# MainBoard.net
KiCad netlist of a schematic drawn in EAGLE
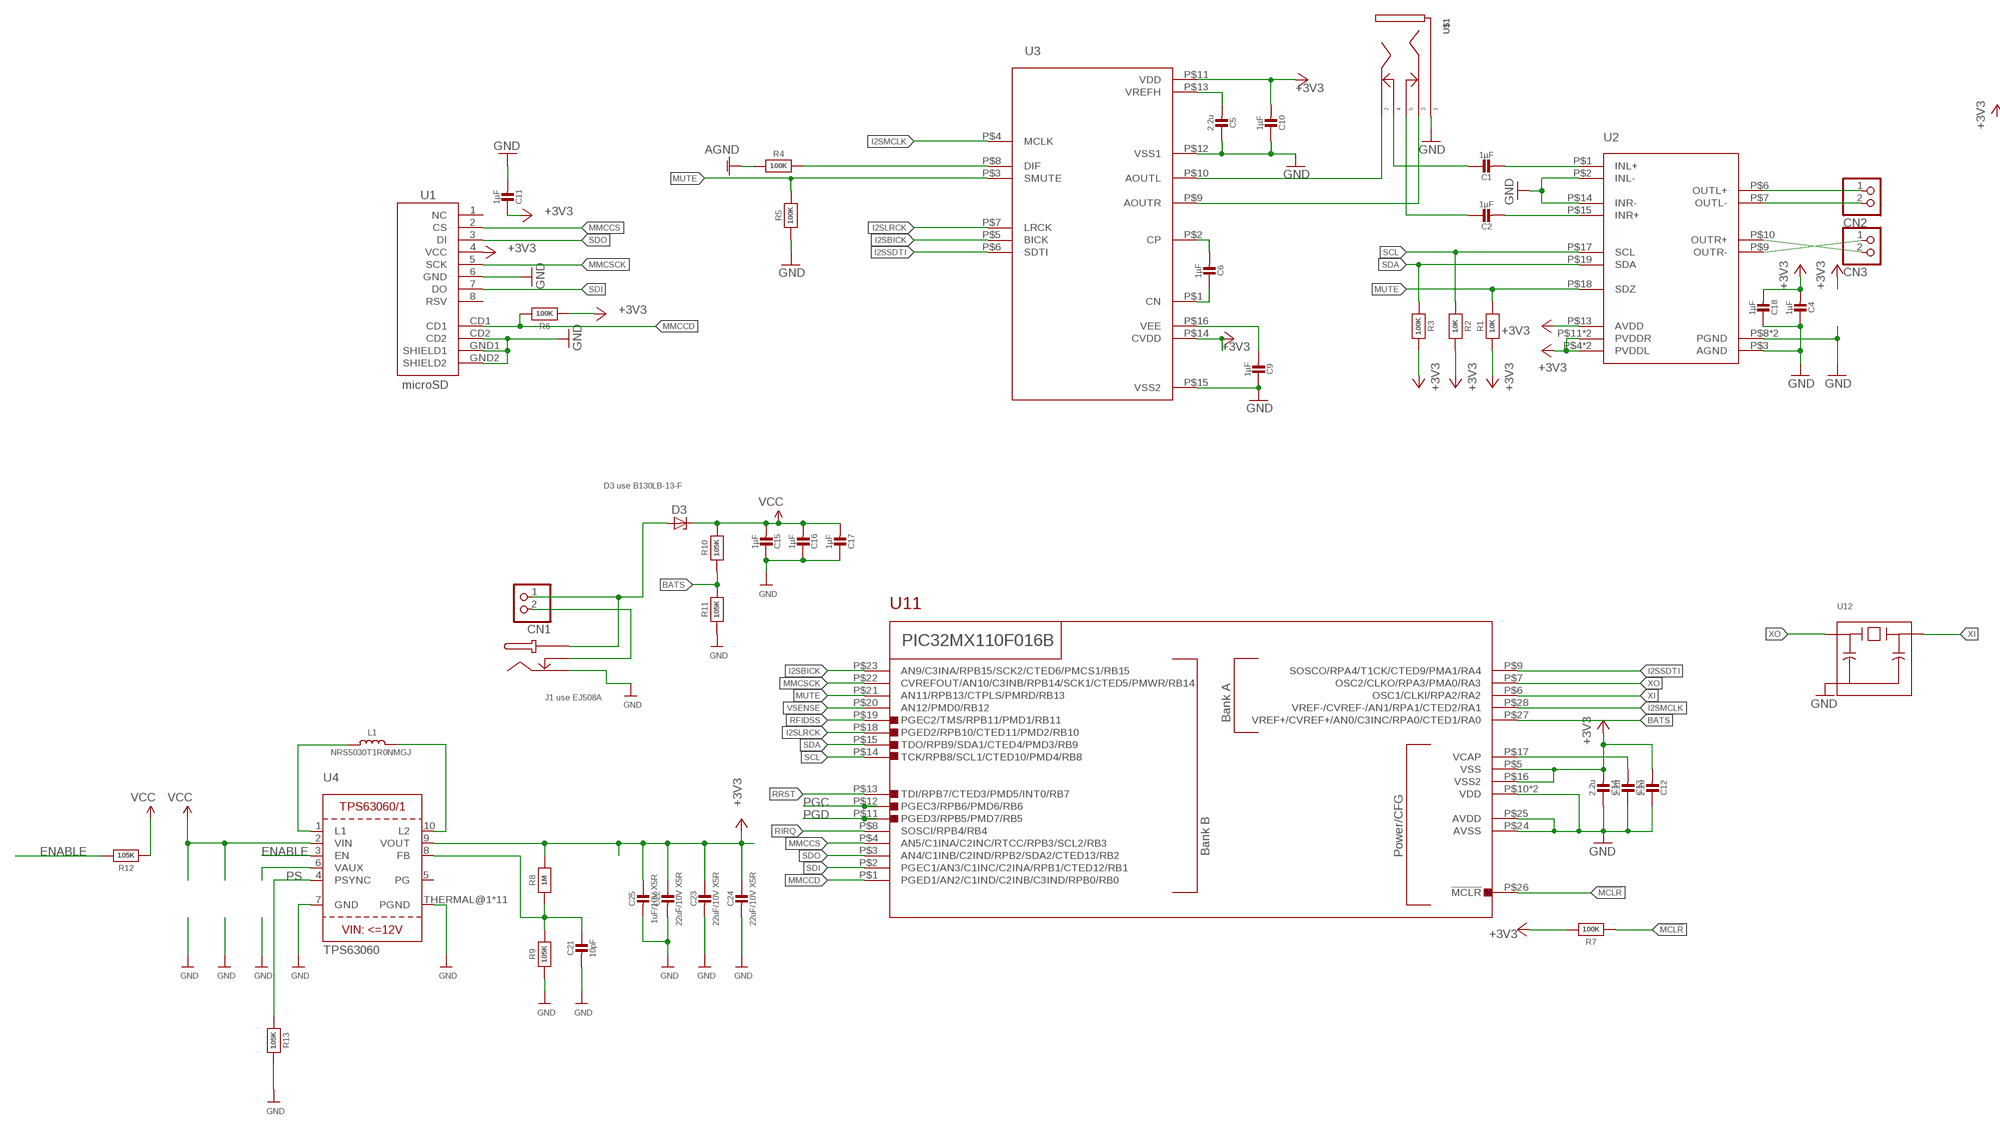
[diagram p0: schematic, sheet 1, part 1 of 2]
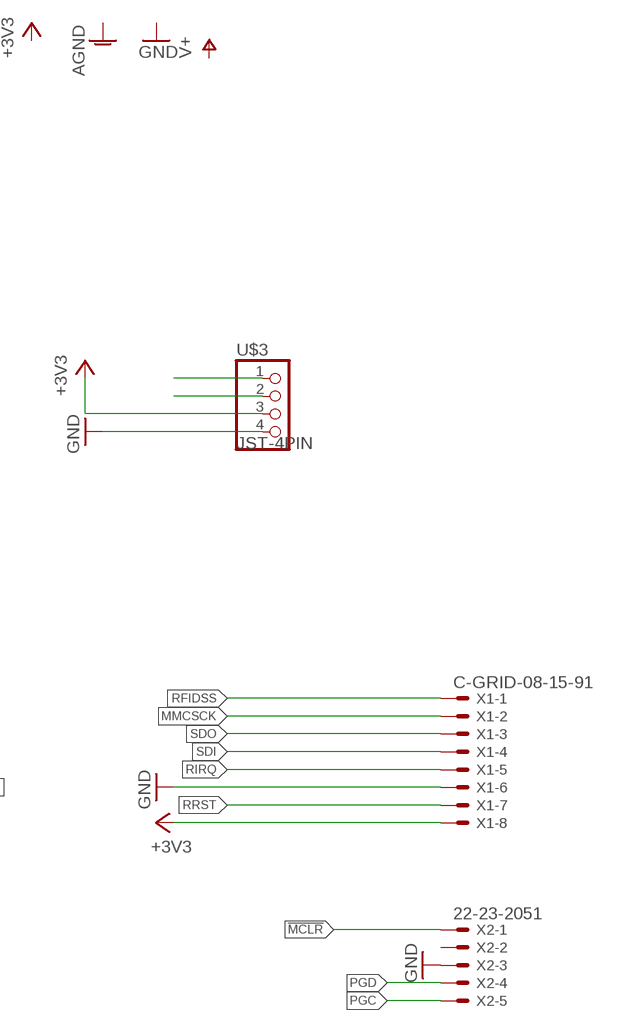
[diagram p1: schematic, sheet 1, part 2 of 2]

(export (version "E")
  (design (tool "Eeschema 10.0.6"))
  (components
    (comp (ref "C1")
      (value "1µF")
      (footprint "eagle-import:0603-NO")
      (libsource (lib "eagle-import") (part "CAP_CERAMIC0603_NO"))
    )
    (comp (ref "C2")
      (value "1µF")
      (footprint "eagle-import:0603-NO")
      (libsource (lib "eagle-import") (part "CAP_CERAMIC0603_NO"))
    )
    (comp (ref "C4")
      (value "1µF")
      (footprint "eagle-import:0805-NO")
      (libsource (lib "eagle-import") (part "CAP_CERAMIC0805-NOOUTLINE"))
    )
    (comp (ref "C5")
      (value "2.2u")
      (footprint "eagle-import:0603-NO")
      (libsource (lib "eagle-import") (part "CAP_CERAMIC0603_NO"))
    )
    (comp (ref "C6")
      (value "1µF")
      (footprint "eagle-import:0603-NO")
      (libsource (lib "eagle-import") (part "CAP_CERAMIC0603_NO"))
    )
    (comp (ref "C9")
      (value "1µF")
      (footprint "eagle-import:0603-NO")
      (libsource (lib "eagle-import") (part "CAP_CERAMIC0603_NO"))
    )
    (comp (ref "C10")
      (value "1µF")
      (footprint "eagle-import:0603-NO")
      (libsource (lib "eagle-import") (part "CAP_CERAMIC0603_NO"))
    )
    (comp (ref "C11")
      (value "1µF")
      (footprint "eagle-import:0603-NO")
      (libsource (lib "eagle-import") (part "CAP_CERAMIC0603_NO"))
    )
    (comp (ref "C12")
      (value "2.2u")
      (footprint "eagle-import:0603-NO")
      (libsource (lib "eagle-import") (part "CAP_CERAMIC0603_NO"))
    )
    (comp (ref "C13")
      (value "2.2u")
      (footprint "eagle-import:0603-NO")
      (libsource (lib "eagle-import") (part "CAP_CERAMIC0603_NO"))
    )
    (comp (ref "C14")
      (value "2.2u")
      (footprint "eagle-import:0603-NO")
      (libsource (lib "eagle-import") (part "CAP_CERAMIC0603_NO"))
    )
    (comp (ref "C15")
      (value "1µF")
      (footprint "eagle-import:0805-NO")
      (libsource (lib "eagle-import") (part "CAP_CERAMIC0805-NOOUTLINE"))
    )
    (comp (ref "C16")
      (value "1µF")
      (footprint "eagle-import:0805-NO")
      (libsource (lib "eagle-import") (part "CAP_CERAMIC0805-NOOUTLINE"))
    )
    (comp (ref "C17")
      (value "1µF")
      (footprint "eagle-import:0805-NO")
      (libsource (lib "eagle-import") (part "CAP_CERAMIC0805-NOOUTLINE"))
    )
    (comp (ref "C18")
      (value "1µF")
      (footprint "eagle-import:0805-NO")
      (libsource (lib "eagle-import") (part "CAP_CERAMIC0805-NOOUTLINE"))
    )
    (comp (ref "C21")
      (value "10pF")
      (footprint "eagle-import:0603-NO")
      (libsource (lib "eagle-import") (part "CAP_CERAMIC0603_NO"))
    )
    (comp (ref "C22")
      (value "22uF/10V X5R")
      (footprint "eagle-import:0805-NO")
      (libsource (lib "eagle-import") (part "CAP_CERAMIC0805-NOOUTLINE"))
    )
    (comp (ref "C23")
      (value "22uF/10V X5R")
      (footprint "eagle-import:0805-NO")
      (libsource (lib "eagle-import") (part "CAP_CERAMIC0805-NOOUTLINE"))
    )
    (comp (ref "C24")
      (value "22uF/10V X5R")
      (footprint "eagle-import:0805-NO")
      (libsource (lib "eagle-import") (part "CAP_CERAMIC0805-NOOUTLINE"))
    )
    (comp (ref "C25")
      (value "1uF/10V X5R")
      (footprint "eagle-import:0805-NO")
      (libsource (lib "eagle-import") (part "CAP_CERAMIC0805-NOOUTLINE"))
    )
    (comp (ref "CN1")
      (value "JST_2PIN-SMT-RA")
      (footprint "eagle-import:JST-PH-2-SMT-RA")
      (libsource (lib "eagle-import") (part "JST_2PIN-SMT-RA"))
    )
    (comp (ref "CN2")
      (value "JST_2PIN-SMT-RA")
      (footprint "eagle-import:JST-PH-2-SMT-RA")
      (libsource (lib "eagle-import") (part "JST_2PIN-SMT-RA"))
    )
    (comp (ref "CN3")
      (value "JST_2PIN-SMT-RA")
      (footprint "eagle-import:JST-PH-2-SMT-RA")
      (libsource (lib "eagle-import") (part "JST_2PIN-SMT-RA"))
    )
    (comp (ref "D3")
      (value "ZENER-DIODESOD80C")
      (footprint "eagle-import:SOD80C")
      (libsource (lib "eagle-import") (part "ZENER-DIODESOD80C"))
    )
    (comp (ref "L1")
      (value "NRS5030T1R0NMGJ")
      (footprint "eagle-import:INDUCTOR_5X5MM_TDK_VLC5045")
      (libsource (lib "eagle-import") (part "INDUCTORTDK_VLC5045"))
    )
    (comp (ref "R1")
      (value "10K")
      (footprint "eagle-import:0603-NO")
      (libsource (lib "eagle-import") (part "RESISTOR_0603_NOOUT"))
    )
    (comp (ref "R2")
      (value "10K")
      (footprint "eagle-import:0603-NO")
      (libsource (lib "eagle-import") (part "RESISTOR_0603_NOOUT"))
    )
    (comp (ref "R3")
      (value "100K")
      (footprint "eagle-import:0603-NO")
      (libsource (lib "eagle-import") (part "RESISTOR_0603_NOOUT"))
    )
    (comp (ref "R4")
      (value "100K")
      (footprint "eagle-import:0603-NO")
      (libsource (lib "eagle-import") (part "RESISTOR_0603_NOOUT"))
    )
    (comp (ref "R5")
      (value "100K")
      (footprint "eagle-import:0603-NO")
      (libsource (lib "eagle-import") (part "RESISTOR_0603_NOOUT"))
    )
    (comp (ref "R6")
      (value "100K")
      (footprint "eagle-import:0603-NO")
      (libsource (lib "eagle-import") (part "RESISTOR_0603_NOOUT"))
    )
    (comp (ref "R7")
      (value "100K")
      (footprint "eagle-import:0603-NO")
      (libsource (lib "eagle-import") (part "RESISTOR_0603_NOOUT"))
    )
    (comp (ref "R8")
      (value "1M")
      (footprint "eagle-import:0603-NO")
      (libsource (lib "eagle-import") (part "RESISTOR_0603_NOOUT"))
    )
    (comp (ref "R9")
      (value "105K")
      (footprint "eagle-import:0603-NO")
      (libsource (lib "eagle-import") (part "RESISTOR_0603_NOOUT"))
    )
    (comp (ref "R10")
      (value "105K")
      (footprint "eagle-import:0603-NO")
      (libsource (lib "eagle-import") (part "RESISTOR_0603_NOOUT"))
    )
    (comp (ref "R11")
      (value "105K")
      (footprint "eagle-import:0603-NO")
      (libsource (lib "eagle-import") (part "RESISTOR_0603_NOOUT"))
    )
    (comp (ref "R12")
      (value "105K")
      (footprint "eagle-import:0603-NO")
      (libsource (lib "eagle-import") (part "RESISTOR_0603_NOOUT"))
    )
    (comp (ref "R13")
      (value "105K")
      (footprint "eagle-import:0603-NO")
      (libsource (lib "eagle-import") (part "RESISTOR_0603_NOOUT"))
    )
    (comp (ref "U$1")
      (value "3,5MMPHONO")
      (footprint "eagle-import:SJ1-351X")
      (libsource (lib "eagle-import") (part "3,5MMPHONO"))
    )
    (comp (ref "U$2")
      (value "PJ-002AH")
      (footprint "eagle-import:PJ-002AH-SMT")
      (libsource (lib "eagle-import") (part "PJ-002AH"))
    )
    (comp (ref "U$3")
      (value "JST-4PIN")
      (footprint "eagle-import:JST-PH-4-SMT-RA")
      (libsource (lib "eagle-import") (part "JST-4PIN"))
    )
    (comp (ref "U1")
      (value "microSD")
      (footprint "eagle-import:MICRO-SD-SOCKET-PP")
      (libsource (lib "eagle-import") (part "USD-SOCKETSMD"))
    )
    (comp (ref "U2")
      (value "TPA2016")
      (footprint "eagle-import:S-PWQFN-N20")
      (libsource (lib "eagle-import") (part "TPA2016"))
    )
    (comp (ref "U3")
      (value "AK4430ET")
      (footprint "eagle-import:16TSSOP")
      (libsource (lib "eagle-import") (part "AK4430ET"))
    )
    (comp (ref "U4")
      (value "TPS63060")
      (footprint "eagle-import:PWSON-N10")
      (libsource (lib "eagle-import") (part "VREG_TPS63060/1"))
    )
    (comp (ref "U11")
      (value "PIC32MX110QFN")
      (footprint "eagle-import:28-QFN")
      (libsource (lib "eagle-import") (part "PIC32MX110QFN"))
    )
    (comp (ref "U12")
      (value "CSTCE")
      (footprint "eagle-import:CSTCE")
      (libsource (lib "eagle-import") (part "CSTCE"))
    )
    (comp (ref "X1")
      (value "C-GRID-08-15-91")
      (footprint "eagle-import:15-91-08")
      (libsource (lib "eagle-import") (part "C-GRID-08-15-91"))
    )
    (comp (ref "X2")
      (value "22-23-2051")
      (footprint "eagle-import:22-23-2051")
      (fields (field (name "MF") "MOLEX"))
      (libsource (lib "eagle-import") (part "22-23-2051"))
    )
  )
  (nets
    (net (code "1") (name "+3V3") (class "Default")
      (node (ref "C10") (pin "2") (pinfunction "2_2") (pintype "passive"))
      (node (ref "C11") (pin "1") (pinfunction "1_1") (pintype "passive"))
      (node (ref "C12") (pin "2") (pinfunction "2_2") (pintype "passive"))
      (node (ref "C14") (pin "2") (pinfunction "2_2") (pintype "passive"))
      (node (ref "C18") (pin "2") (pinfunction "2_2") (pintype "passive"))
      (node (ref "C22") (pin "1") (pinfunction "1_1") (pintype "passive"))
      (node (ref "C23") (pin "1") (pinfunction "1_1") (pintype "passive"))
      (node (ref "C24") (pin "1") (pinfunction "1_1") (pintype "passive"))
      (node (ref "C25") (pin "1") (pinfunction "1_1") (pintype "passive"))
      (node (ref "C4") (pin "2") (pinfunction "2_2") (pintype "passive"))
      (node (ref "R1") (pin "1") (pinfunction "1_1") (pintype "passive"))
      (node (ref "R2") (pin "2") (pinfunction "2_2") (pintype "passive"))
      (node (ref "R3") (pin "2") (pinfunction "2_2") (pintype "passive"))
      (node (ref "R6") (pin "1") (pinfunction "1_1") (pintype "passive"))
      (node (ref "R7") (pin "2") (pinfunction "2_2") (pintype "passive"))
      (node (ref "R8") (pin "2") (pinfunction "2_2") (pintype "passive"))
      (node (ref "U$3") (pin "3") (pinfunction "3_3") (pintype "passive"))
      (node (ref "U1") (pin "4") (pinfunction "VCC_4") (pintype "bidirectional"))
      (node (ref "U11") (pin "P$16") (pinfunction "VSS2_P$16") (pintype "bidirectional"))
      (node (ref "U11") (pin "P$5") (pinfunction "VSS_P$5") (pintype "bidirectional"))
      (node (ref "U2") (pin "P$11") (pinfunction "PVDDR_P$11") (pintype "bidirectional"))
      (node (ref "U2") (pin "P$12") (pinfunction "PVDDR_P$12") (pintype "bidirectional"))
      (node (ref "U2") (pin "P$13") (pinfunction "AVDD_P$13") (pintype "bidirectional"))
      (node (ref "U2") (pin "P$4") (pinfunction "PVDDL_P$4") (pintype "bidirectional"))
      (node (ref "U2") (pin "P$5") (pinfunction "PVDDL_P$5") (pintype "bidirectional"))
      (node (ref "U3") (pin "P$11") (pinfunction "VDD_P$11") (pintype "bidirectional"))
      (node (ref "U3") (pin "P$14") (pinfunction "CVDD_P$14") (pintype "bidirectional"))
      (node (ref "U4") (pin "9") (pinfunction "VOUT_9") (pintype "power_in"))
      (node (ref "X1") (pin "8") (pinfunction "S_8") (pintype "passive"))
    )
    (net (code "2") (name "/ENABLE") (class "Default")
      (node (ref "R12") (pin "2") (pinfunction "2_2") (pintype "passive"))
      (node (ref "U4") (pin "3") (pinfunction "EN_3") (pintype "input"))
    )
    (net (code "3") (name "/PS") (class "Default")
      (node (ref "R13") (pin "1") (pinfunction "1_1") (pintype "passive"))
      (node (ref "U4") (pin "4") (pinfunction "PSYNC_4") (pintype "input"))
    )
    (net (code "4") (name "/~{MCLR}") (class "Default")
      (node (ref "R7") (pin "1") (pinfunction "1_1") (pintype "passive"))
      (node (ref "U11") (pin "P$26") (pinfunction "~{MCLR}_P$26") (pintype "bidirectional"))
      (node (ref "X2") (pin "1") (pinfunction "S_1") (pintype "passive"))
    )
    (net (code "5") (name "AGND") (class "Default")
      (node (ref "R4") (pin "1") (pinfunction "1_1") (pintype "passive"))
    )
    (net (code "6") (name "BATS") (class "Default")
      (node (ref "R10") (pin "1") (pinfunction "1_1") (pintype "passive"))
      (node (ref "R11") (pin "2") (pinfunction "2_2") (pintype "passive"))
      (node (ref "U11") (pin "P$27") (pinfunction "VREF+/CVREF+/AN0/C3INC/RPA0/CTED1/RA0_P$27") (pintype "bidirectional"))
    )
    (net (code "7") (name "GND") (class "Default")
      (node (ref "C10") (pin "1") (pinfunction "1_1") (pintype "passive"))
      (node (ref "C11") (pin "2") (pinfunction "2_2") (pintype "passive"))
      (node (ref "C12") (pin "1") (pinfunction "1_1") (pintype "passive"))
      (node (ref "C13") (pin "1") (pinfunction "1_1") (pintype "passive"))
      (node (ref "C14") (pin "1") (pinfunction "1_1") (pintype "passive"))
      (node (ref "C15") (pin "1") (pinfunction "1_1") (pintype "passive"))
      (node (ref "C16") (pin "1") (pinfunction "1_1") (pintype "passive"))
      (node (ref "C17") (pin "1") (pinfunction "1_1") (pintype "passive"))
      (node (ref "C18") (pin "1") (pinfunction "1_1") (pintype "passive"))
      (node (ref "C21") (pin "2") (pinfunction "2_2") (pintype "passive"))
      (node (ref "C22") (pin "2") (pinfunction "2_2") (pintype "passive"))
      (node (ref "C23") (pin "2") (pinfunction "2_2") (pintype "passive"))
      (node (ref "C24") (pin "2") (pinfunction "2_2") (pintype "passive"))
      (node (ref "C25") (pin "2") (pinfunction "2_2") (pintype "passive"))
      (node (ref "C4") (pin "1") (pinfunction "1_1") (pintype "passive"))
      (node (ref "C5") (pin "1") (pinfunction "1_1") (pintype "passive"))
      (node (ref "C9") (pin "1") (pinfunction "1_1") (pintype "passive"))
      (node (ref "R11") (pin "1") (pinfunction "1_1") (pintype "passive"))
      (node (ref "R13") (pin "2") (pinfunction "2_2") (pintype "passive"))
      (node (ref "R5") (pin "1") (pinfunction "1_1") (pintype "passive"))
      (node (ref "R9") (pin "1") (pinfunction "1_1") (pintype "passive"))
      (node (ref "U$1") (pin "1") (pinfunction "1_1") (pintype "bidirectional"))
      (node (ref "U$2") (pin "2") (pinfunction "2_2") (pintype "bidirectional"))
      (node (ref "U$3") (pin "4") (pinfunction "4_4") (pintype "passive"))
      (node (ref "U1") (pin "6") (pinfunction "GND_6") (pintype "bidirectional"))
      (node (ref "U1") (pin "CD2") (pinfunction "CD2_CD2") (pintype "bidirectional"))
      (node (ref "U1") (pin "GND1") (pinfunction "SHIELD1_GND1") (pintype "bidirectional"))
      (node (ref "U1") (pin "GND2") (pinfunction "SHIELD2_GND2") (pintype "bidirectional"))
      (node (ref "U11") (pin "P$10") (pinfunction "VDD_P$10") (pintype "bidirectional"))
      (node (ref "U11") (pin "P$24") (pinfunction "AVSS_P$24") (pintype "bidirectional"))
      (node (ref "U11") (pin "P$25") (pinfunction "AVDD_P$25") (pintype "bidirectional"))
      (node (ref "U11") (pin "P$29") (pinfunction "VDD_P$29") (pintype "bidirectional"))
      (node (ref "U12") (pin "2") (pinfunction "2_2") (pintype "bidirectional"))
      (node (ref "U2") (pin "P$14") (pinfunction "INR-_P$14") (pintype "bidirectional"))
      (node (ref "U2") (pin "P$2") (pinfunction "INL-_P$2") (pintype "bidirectional"))
      (node (ref "U2") (pin "P$21") (pinfunction "PGND_P$21") (pintype "bidirectional"))
      (node (ref "U2") (pin "P$3") (pinfunction "AGND_P$3") (pintype "bidirectional"))
      (node (ref "U2") (pin "P$8") (pinfunction "PGND_P$8") (pintype "bidirectional"))
      (node (ref "U3") (pin "P$12") (pinfunction "VSS1_P$12") (pintype "bidirectional"))
      (node (ref "U3") (pin "P$15") (pinfunction "VSS2_P$15") (pintype "bidirectional"))
      (node (ref "U4") (pin "7") (pinfunction "GND_7") (pintype "power_in"))
      (node (ref "U4") (pin "THERMAL@1") (pinfunction "PGND_THERMAL@1") (pintype "power_in"))
      (node (ref "U4") (pin "THERMAL@10") (pinfunction "PGND_THERMAL@10") (pintype "power_in"))
      (node (ref "U4") (pin "THERMAL@11") (pinfunction "PGND_THERMAL@11") (pintype "power_in"))
      (node (ref "U4") (pin "THERMAL@12") (pinfunction "PGND_THERMAL@12") (pintype "power_in"))
      (node (ref "U4") (pin "THERMAL@13") (pinfunction "PGND_THERMAL@13") (pintype "power_in"))
      (node (ref "U4") (pin "THERMAL@14") (pinfunction "PGND_THERMAL@14") (pintype "power_in"))
      (node (ref "U4") (pin "THERMAL@5") (pinfunction "PGND_THERMAL@5") (pintype "power_in"))
      (node (ref "U4") (pin "THERMAL@6") (pinfunction "PGND_THERMAL@6") (pintype "power_in"))
      (node (ref "U4") (pin "THERMAL@7") (pinfunction "PGND_THERMAL@7") (pintype "power_in"))
      (node (ref "U4") (pin "THERMAL@8") (pinfunction "PGND_THERMAL@8") (pintype "power_in"))
      (node (ref "U4") (pin "THERMAL@9") (pinfunction "PGND_THERMAL@9") (pintype "power_in"))
      (node (ref "X1") (pin "6") (pinfunction "S_6") (pintype "passive"))
      (node (ref "X2") (pin "3") (pinfunction "S_3") (pintype "passive"))
    )
    (net (code "8") (name "I2SBICK") (class "Default")
      (node (ref "U11") (pin "P$23") (pinfunction "AN9/C3INA/RPB15/SCK2/CTED6/PMCS1/RB15_P$23") (pintype "bidirectional"))
      (node (ref "U3") (pin "P$5") (pinfunction "BICK_P$5") (pintype "bidirectional"))
    )
    (net (code "9") (name "I2SLRCK") (class "Default")
      (node (ref "U11") (pin "P$18") (pinfunction "PGED2/RPB10/CTED11/PMD2/RB10_P$18") (pintype "bidirectional"))
      (node (ref "U3") (pin "P$7") (pinfunction "LRCK_P$7") (pintype "bidirectional"))
    )
    (net (code "10") (name "I2SMCLK") (class "Default")
      (node (ref "U11") (pin "P$28") (pinfunction "VREF-/CVREF-/AN1/RPA1/CTED2/RA1_P$28") (pintype "bidirectional"))
      (node (ref "U3") (pin "P$4") (pinfunction "MCLK_P$4") (pintype "bidirectional"))
    )
    (net (code "11") (name "I2SSDTI") (class "Default")
      (node (ref "U11") (pin "P$9") (pinfunction "SOSCO/RPA4/T1CK/CTED9/PMA1/RA4_P$9") (pintype "bidirectional"))
      (node (ref "U3") (pin "P$6") (pinfunction "SDTI_P$6") (pintype "bidirectional"))
    )
    (net (code "12") (name "MMCCD") (class "Default")
      (node (ref "R6") (pin "2") (pinfunction "2_2") (pintype "passive"))
      (node (ref "U1") (pin "CD1") (pinfunction "CD1_CD1") (pintype "bidirectional"))
      (node (ref "U11") (pin "P$1") (pinfunction "PGED1/AN2/C1IND/C2INB/C3IND/RPB0/RB0_P$1") (pintype "bidirectional"))
    )
    (net (code "13") (name "MMCCS") (class "Default")
      (node (ref "U1") (pin "2") (pinfunction "CS_2") (pintype "bidirectional"))
      (node (ref "U11") (pin "P$4") (pinfunction "AN5/C1INA/C2INC/RTCC/RPB3/SCL2/RB3_P$4") (pintype "bidirectional"))
    )
    (net (code "14") (name "MMCSCK") (class "Default")
      (node (ref "U1") (pin "5") (pinfunction "SCK_5") (pintype "bidirectional"))
      (node (ref "U11") (pin "P$22") (pinfunction "CVREFOUT/AN10/C3INB/RPB14/SCK1/CTED5/PMWR/RB14_P$22") (pintype "bidirectional"))
      (node (ref "X1") (pin "2") (pinfunction "S_2") (pintype "passive"))
    )
    (net (code "15") (name "MUTE") (class "Default")
      (node (ref "R1") (pin "2") (pinfunction "2_2") (pintype "passive"))
      (node (ref "R5") (pin "2") (pinfunction "2_2") (pintype "passive"))
      (node (ref "U11") (pin "P$21") (pinfunction "AN11/RPB13/CTPLS/PMRD/RB13_P$21") (pintype "bidirectional"))
      (node (ref "U2") (pin "P$18") (pinfunction "SDZ_P$18") (pintype "bidirectional"))
      (node (ref "U3") (pin "P$3") (pinfunction "SMUTE_P$3") (pintype "bidirectional"))
    )
    (net (code "16") (name "Net-(C1-Pad1)") (class "Default")
      (node (ref "C1") (pin "1") (pinfunction "1_1") (pintype "passive"))
      (node (ref "U$1") (pin "4") (pinfunction "4_4") (pintype "bidirectional"))
    )
    (net (code "17") (name "Net-(C2-Pad1)") (class "Default")
      (node (ref "C2") (pin "1") (pinfunction "1_1") (pintype "passive"))
      (node (ref "U$1") (pin "5") (pinfunction "5_5") (pintype "bidirectional"))
    )
    (net (code "18") (name "Net-(CN1-1)") (class "Default")
      (node (ref "CN1") (pin "2") (pinfunction "1_2") (pintype "passive"))
      (node (ref "U$2") (pin "3") (pinfunction "3_3") (pintype "bidirectional"))
    )
    (net (code "19") (name "Net-(CN1-2)") (class "Default")
      (node (ref "CN1") (pin "1") (pinfunction "2_1") (pintype "passive"))
      (node (ref "D3") (pin "A") (pinfunction "A_A") (pintype "passive"))
      (node (ref "U$2") (pin "1") (pinfunction "1_1") (pintype "bidirectional"))
      (node (ref "U$2") (pin "A") (pinfunction "1_A") (pintype "bidirectional"))
    )
    (net (code "20") (name "Net-(CN2-1)") (class "Default")
      (node (ref "CN2") (pin "2") (pinfunction "1_2") (pintype "passive"))
      (node (ref "U2") (pin "P$7") (pinfunction "OUTL-_P$7") (pintype "bidirectional"))
    )
    (net (code "21") (name "Net-(CN2-2)") (class "Default")
      (node (ref "CN2") (pin "1") (pinfunction "2_1") (pintype "passive"))
      (node (ref "U2") (pin "P$6") (pinfunction "OUTL+_P$6") (pintype "bidirectional"))
    )
    (net (code "22") (name "Net-(CN3-1)") (class "Default")
      (node (ref "CN3") (pin "2") (pinfunction "1_2") (pintype "passive"))
      (node (ref "U2") (pin "P$10") (pinfunction "OUTR+_P$10") (pintype "bidirectional"))
    )
    (net (code "23") (name "Net-(CN3-2)") (class "Default")
      (node (ref "CN3") (pin "1") (pinfunction "2_1") (pintype "passive"))
      (node (ref "U2") (pin "P$9") (pinfunction "OUTR-_P$9") (pintype "bidirectional"))
    )
    (net (code "24") (name "Net-(L1-1)") (class "Default")
      (node (ref "L1") (pin "P$1") (pinfunction "1_P$1") (pintype "passive"))
      (node (ref "U4") (pin "1") (pinfunction "L1_1") (pintype "input"))
    )
    (net (code "25") (name "Net-(L1-2)") (class "Default")
      (node (ref "L1") (pin "P$2") (pinfunction "2_P$2") (pintype "passive"))
      (node (ref "U4") (pin "10") (pinfunction "L2_10") (pintype "input"))
    )
    (net (code "26") (name "Net-(U2-INL+)") (class "Default")
      (node (ref "C1") (pin "2") (pinfunction "2_2") (pintype "passive"))
      (node (ref "U2") (pin "P$1") (pinfunction "INL+_P$1") (pintype "bidirectional"))
    )
    (net (code "27") (name "Net-(U2-INR+)") (class "Default")
      (node (ref "C2") (pin "2") (pinfunction "2_2") (pintype "passive"))
      (node (ref "U2") (pin "P$15") (pinfunction "INR+_P$15") (pintype "bidirectional"))
    )
    (net (code "28") (name "Net-(U3-AOUTL)") (class "Default")
      (node (ref "U$1") (pin "2") (pinfunction "2_2") (pintype "bidirectional"))
      (node (ref "U3") (pin "P$10") (pinfunction "AOUTL_P$10") (pintype "bidirectional"))
    )
    (net (code "29") (name "Net-(U3-AOUTR)") (class "Default")
      (node (ref "U$1") (pin "3") (pinfunction "3_3") (pintype "bidirectional"))
      (node (ref "U3") (pin "P$9") (pinfunction "AOUTR_P$9") (pintype "bidirectional"))
    )
    (net (code "30") (name "Net-(U3-CN)") (class "Default")
      (node (ref "C6") (pin "1") (pinfunction "1_1") (pintype "passive"))
      (node (ref "U3") (pin "P$1") (pinfunction "CN_P$1") (pintype "bidirectional"))
    )
    (net (code "31") (name "Net-(U3-CP)") (class "Default")
      (node (ref "C6") (pin "2") (pinfunction "2_2") (pintype "passive"))
      (node (ref "U3") (pin "P$2") (pinfunction "CP_P$2") (pintype "bidirectional"))
    )
    (net (code "32") (name "Net-(U3-DIF)") (class "Default")
      (node (ref "R4") (pin "2") (pinfunction "2_2") (pintype "passive"))
      (node (ref "U3") (pin "P$8") (pinfunction "DIF_P$8") (pintype "bidirectional"))
    )
    (net (code "33") (name "Net-(U3-VEE)") (class "Default")
      (node (ref "C9") (pin "2") (pinfunction "2_2") (pintype "passive"))
      (node (ref "U3") (pin "P$16") (pinfunction "VEE_P$16") (pintype "bidirectional"))
    )
    (net (code "34") (name "Net-(U3-VREFH)") (class "Default")
      (node (ref "C5") (pin "2") (pinfunction "2_2") (pintype "passive"))
      (node (ref "U3") (pin "P$13") (pinfunction "VREFH_P$13") (pintype "bidirectional"))
    )
    (net (code "35") (name "Net-(U4-FB)") (class "Default")
      (node (ref "C21") (pin "1") (pinfunction "1_1") (pintype "passive"))
      (node (ref "R8") (pin "1") (pinfunction "1_1") (pintype "passive"))
      (node (ref "R9") (pin "2") (pinfunction "2_2") (pintype "passive"))
      (node (ref "U4") (pin "8") (pinfunction "FB_8") (pintype "input"))
    )
    (net (code "36") (name "Net-(U11-VCAP)") (class "Default")
      (node (ref "C13") (pin "2") (pinfunction "2_2") (pintype "passive"))
      (node (ref "U11") (pin "P$17") (pinfunction "VCAP_P$17") (pintype "bidirectional"))
    )
    (net (code "37") (name "PGC") (class "Default")
      (node (ref "U11") (pin "P$12") (pinfunction "PGEC3/RPB6/PMD6/RB6_P$12") (pintype "bidirectional"))
      (node (ref "X2") (pin "5") (pinfunction "S_5") (pintype "passive"))
    )
    (net (code "38") (name "PGD") (class "Default")
      (node (ref "U11") (pin "P$11") (pinfunction "PGED3/RPB5/PMD7/RB5_P$11") (pintype "bidirectional"))
      (node (ref "X2") (pin "4") (pinfunction "S_4") (pintype "passive"))
    )
    (net (code "39") (name "RFIDSS") (class "Default")
      (node (ref "U11") (pin "P$19") (pinfunction "PGEC2/TMS/RPB11/PMD1/RB11_P$19") (pintype "bidirectional"))
      (node (ref "X1") (pin "1") (pinfunction "S_1") (pintype "passive"))
    )
    (net (code "40") (name "RIRQ") (class "Default")
      (node (ref "U11") (pin "P$8") (pinfunction "SOSCI/RPB4/RB4_P$8") (pintype "bidirectional"))
      (node (ref "X1") (pin "5") (pinfunction "S_5") (pintype "passive"))
    )
    (net (code "41") (name "RRST") (class "Default")
      (node (ref "U11") (pin "P$13") (pinfunction "TDI/RPB7/CTED3/PMD5/INT0/RB7_P$13") (pintype "bidirectional"))
      (node (ref "X1") (pin "7") (pinfunction "S_7") (pintype "passive"))
    )
    (net (code "42") (name "SCL") (class "Default")
      (node (ref "R2") (pin "1") (pinfunction "1_1") (pintype "passive"))
      (node (ref "U$3") (pin "2") (pinfunction "2_2") (pintype "passive"))
      (node (ref "U11") (pin "P$14") (pinfunction "TCK/RPB8/SCL1/CTED10/PMD4/RB8_P$14") (pintype "bidirectional"))
      (node (ref "U2") (pin "P$17") (pinfunction "SCL_P$17") (pintype "bidirectional"))
    )
    (net (code "43") (name "SDA") (class "Default")
      (node (ref "R3") (pin "1") (pinfunction "1_1") (pintype "passive"))
      (node (ref "U$3") (pin "1") (pinfunction "1_1") (pintype "passive"))
      (node (ref "U11") (pin "P$15") (pinfunction "TDO/RPB9/SDA1/CTED4/PMD3/RB9_P$15") (pintype "bidirectional"))
      (node (ref "U2") (pin "P$19") (pinfunction "SDA_P$19") (pintype "bidirectional"))
    )
    (net (code "44") (name "SDI") (class "Default")
      (node (ref "U1") (pin "7") (pinfunction "DO_7") (pintype "bidirectional"))
      (node (ref "U11") (pin "P$2") (pinfunction "PGEC1/AN3/C1INC/C2INA/RPB1/CTED12/RB1_P$2") (pintype "bidirectional"))
      (node (ref "X1") (pin "4") (pinfunction "S_4") (pintype "passive"))
    )
    (net (code "45") (name "SDO") (class "Default")
      (node (ref "U1") (pin "3") (pinfunction "DI_3") (pintype "bidirectional"))
      (node (ref "U11") (pin "P$3") (pinfunction "AN4/C1INB/C2IND/RPB2/SDA2/CTED13/RB2_P$3") (pintype "bidirectional"))
      (node (ref "X1") (pin "3") (pinfunction "S_3") (pintype "passive"))
    )
    (net (code "47") (name "VCC") (class "Default")
      (node (ref "C15") (pin "2") (pinfunction "2_2") (pintype "passive"))
      (node (ref "C16") (pin "2") (pinfunction "2_2") (pintype "passive"))
      (node (ref "C17") (pin "2") (pinfunction "2_2") (pintype "passive"))
      (node (ref "D3") (pin "C") (pinfunction "C_C") (pintype "passive"))
      (node (ref "R10") (pin "2") (pinfunction "2_2") (pintype "passive"))
      (node (ref "R12") (pin "1") (pinfunction "1_1") (pintype "passive"))
      (node (ref "U4") (pin "2") (pinfunction "VIN_2") (pintype "power_in"))
    )
    (net (code "48") (name "VSENSE") (class "Default")
      (node (ref "U11") (pin "P$20") (pinfunction "AN12/PMD0/RB12_P$20") (pintype "bidirectional"))
    )
    (net (code "49") (name "XI") (class "Default")
      (node (ref "U11") (pin "P$6") (pinfunction "OSC1/CLKI/RPA2/RA2_P$6") (pintype "bidirectional"))
      (node (ref "U12") (pin "3") (pinfunction "3_3") (pintype "bidirectional"))
    )
    (net (code "50") (name "XO") (class "Default")
      (node (ref "U11") (pin "P$7") (pinfunction "OSC2/CLKO/RPA3/PMA0/RA3_P$7") (pintype "bidirectional"))
      (node (ref "U12") (pin "1") (pinfunction "1_1") (pintype "bidirectional"))
    )
    (net (code "51") (name "unconnected-(U1-NC-Pad1)") (class "Default")
      (node (ref "U1") (pin "1") (pinfunction "NC_1") (pintype "bidirectional"))
    )
    (net (code "52") (name "unconnected-(U1-RSV-Pad8)") (class "Default")
      (node (ref "U1") (pin "8") (pinfunction "RSV_8") (pintype "bidirectional"))
    )
    (net (code "53") (name "unconnected-(U4-PG-Pad5)") (class "Default")
      (node (ref "U4") (pin "5") (pinfunction "PG_5") (pintype "open_collector"))
    )
    (net (code "54") (name "unconnected-(U4-VAUX-Pad6)") (class "Default")
      (node (ref "U4") (pin "6") (pinfunction "VAUX_6") (pintype "passive"))
    )
    (net (code "55") (name "unconnected-(X2B-S-Pad2)") (class "Default")
      (node (ref "X2") (pin "2") (pinfunction "S_2") (pintype "passive"))
    )
  )
)
